# 02_MCU.net
KiCad netlist of a schematic drawn in Altium Designer
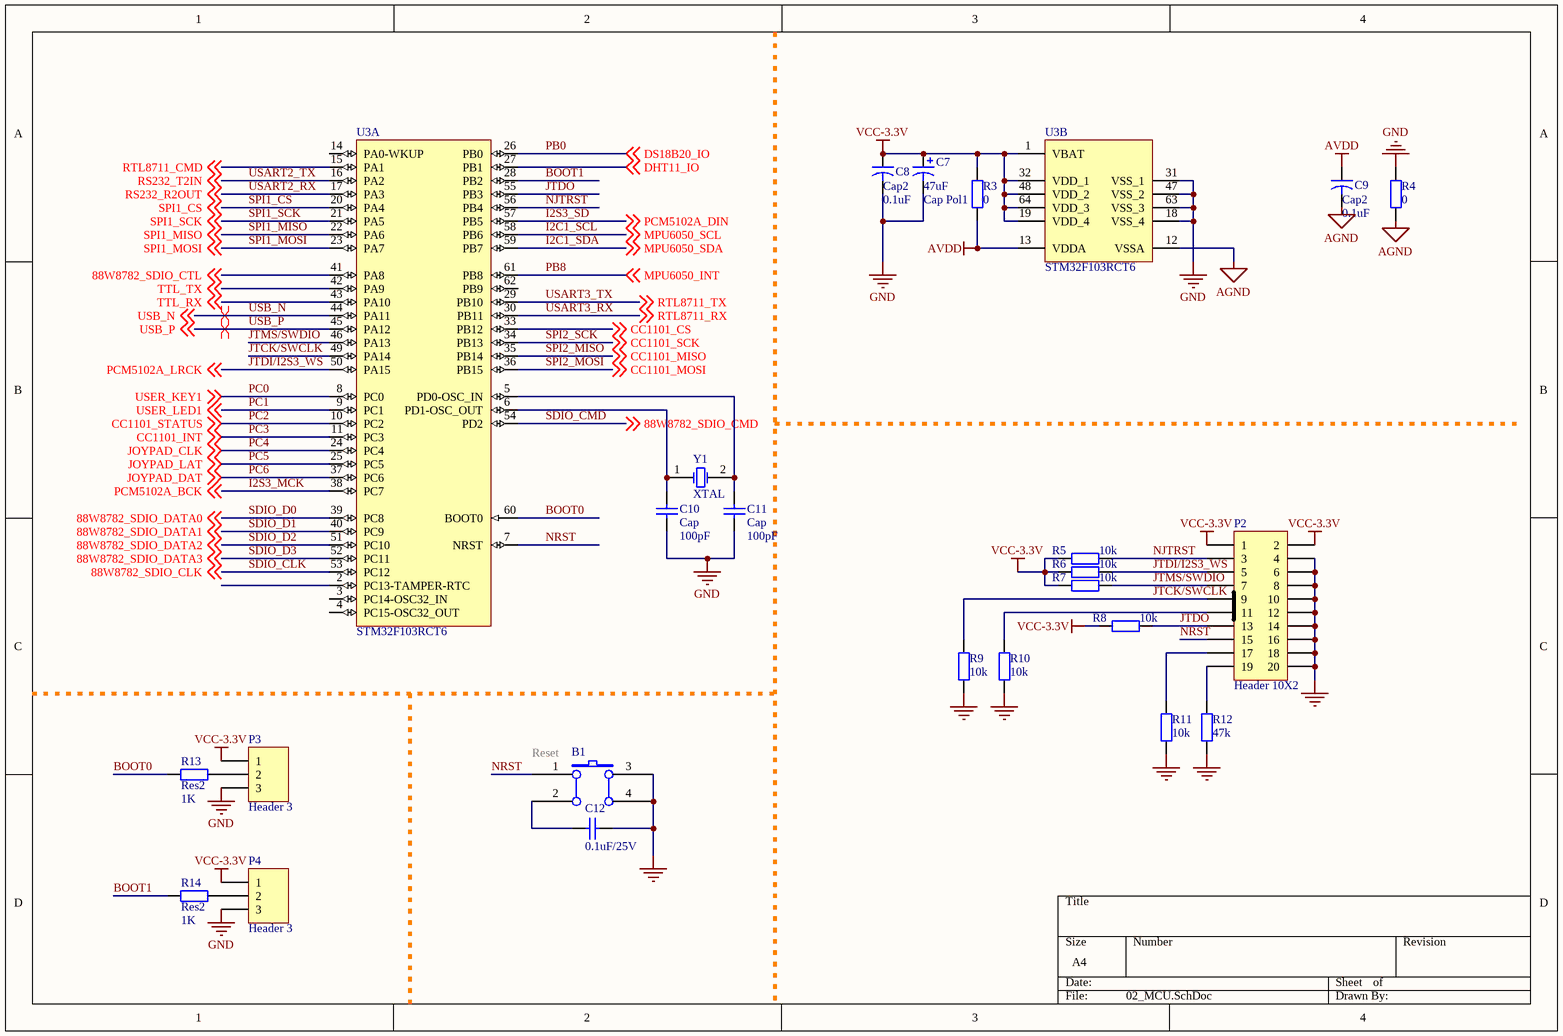
[diagram p0: 02_MCU.SchDoc]

(export (version "E")
  (design (tool "Eeschema 10.0.6"))
  (components
    (comp (ref "B1")
      (value "Reset")
      (footprint "Miscellaneous Modules:SWITCH-0.65/0.45")
      (description "Tactile Switch")
      (libsource (lib "Miscellaneous Modules") (part "SW PUSHBUTTON"))
    )
    (comp (ref "C7")
      (value "Cap Pol1")
      (footprint "RB2.5-6.3")
      (description "Polarized Capacitor (Radial)")
      (fields (field (name "ALTIUM_VALUE") "47uF") (field (name "PUBLISHER") "Altium Limited"))
      (libsource (lib "Miscellaneous Devices") (part "Cap Pol1"))
    )
    (comp (ref "C8")
      (value "Cap2")
      (footprint "CAPR5-4X5")
      (description "Capacitor")
      (fields (field (name "ALTIUM_VALUE") "0.1uF") (field (name "PUBLISHER") "Altium Limited"))
      (libsource (lib "Miscellaneous Devices") (part "Cap2"))
    )
    (comp (ref "C9")
      (value "Cap2")
      (footprint "RAD-0.1")
      (description "Capacitor")
      (fields (field (name "ALTIUM_VALUE") "0.1uF") (field (name "PUBLISHER") "Altium Limited"))
      (libsource (lib "Miscellaneous Devices") (part "Cap2"))
    )
    (comp (ref "C10")
      (value "Cap")
      (footprint "RAD-0.1")
      (description "Capacitor")
      (fields (field (name "ALTIUM_VALUE") "100pF") (field (name "PUBLISHER") "Altium Limited"))
      (libsource (lib "Miscellaneous Devices") (part "Cap"))
    )
    (comp (ref "C11")
      (value "Cap")
      (footprint "RAD-0.1")
      (description "Capacitor")
      (fields (field (name "ALTIUM_VALUE") "100pF") (field (name "PUBLISHER") "Altium Limited"))
      (libsource (lib "Miscellaneous Devices") (part "Cap"))
    )
    (comp (ref "C12")
      (value "0.1uF/25V")
      (footprint "RAD-0.1")
      (description "Capacitor")
      (fields (field (name "PUBLISHER") "Altium Limited"))
      (libsource (lib "Miscellaneous Devices") (part "CAP"))
    )
    (comp (ref "P2")
      (value "Header 10X2")
      (footprint "MHDR2X10_2.54")
      (description "Header, 10-Pin, Dual row")
      (fields (field (name "PUBLISHER") "Altium Limited"))
      (libsource (lib "Miscellaneous Connectors") (part "Header 10X2"))
    )
    (comp (ref "P3")
      (value "Header 3")
      (footprint "HDR1X3")
      (description "Header, 3-Pin")
      (fields (field (name "PUBLISHER") "Altium Limited"))
      (libsource (lib "Miscellaneous Connectors") (part "Header 3"))
    )
    (comp (ref "P4")
      (value "Header 3")
      (footprint "HDR1X3")
      (description "Header, 3-Pin")
      (fields (field (name "PUBLISHER") "Altium Limited"))
      (libsource (lib "Miscellaneous Connectors") (part "Header 3"))
    )
    (comp (ref "R3")
      (value "0")
      (footprint "AXIAL-0.3")
      (description "贴片电阻")
      (fields (field (name "PUBLISHER") "Altium Limited"))
      (libsource (lib "fszhang") (part "Res1"))
    )
    (comp (ref "R4")
      (value "0")
      (footprint "AXIAL-0.3")
      (description "贴片电阻")
      (fields (field (name "Comment") "10k") (field (name "PUBLISHER") "Altium Limited"))
      (libsource (lib "fszhang") (part "Res1"))
    )
    (comp (ref "R5")
      (value "10k")
      (footprint "AXIAL-0.3")
      (description "贴片电阻")
      (fields (field (name "PUBLISHER") "Altium Limited"))
      (libsource (lib "") (part "Res1_1"))
    )
    (comp (ref "R6")
      (value "10k")
      (footprint "AXIAL-0.3")
      (description "贴片电阻")
      (fields (field (name "PUBLISHER") "Altium Limited"))
      (libsource (lib "") (part "Res1_1"))
    )
    (comp (ref "R7")
      (value "10k")
      (footprint "AXIAL-0.3")
      (description "贴片电阻")
      (fields (field (name "PUBLISHER") "Altium Limited"))
      (libsource (lib "") (part "Res1_1"))
    )
    (comp (ref "R8")
      (value "10k")
      (footprint "AXIAL-0.3")
      (description "贴片电阻")
      (fields (field (name "PUBLISHER") "Altium Limited"))
      (libsource (lib "") (part "Res1_1"))
    )
    (comp (ref "R9")
      (value "10k")
      (footprint "AXIAL-0.3")
      (description "贴片电阻")
      (fields (field (name "PUBLISHER") "Altium Limited"))
      (libsource (lib "fszhang") (part "Res1"))
    )
    (comp (ref "R10")
      (value "10k")
      (footprint "AXIAL-0.3")
      (description "贴片电阻")
      (fields (field (name "PUBLISHER") "Altium Limited"))
      (libsource (lib "fszhang") (part "Res1"))
    )
    (comp (ref "R11")
      (value "10k")
      (footprint "AXIAL-0.3")
      (description "贴片电阻")
      (fields (field (name "PUBLISHER") "Altium Limited"))
      (libsource (lib "fszhang") (part "Res1"))
    )
    (comp (ref "R12")
      (value "47k")
      (footprint "AXIAL-0.3")
      (description "贴片电阻")
      (fields (field (name "Comment") "10k") (field (name "PUBLISHER") "Altium Limited"))
      (libsource (lib "fszhang") (part "Res1"))
    )
    (comp (ref "R13")
      (value "Res2")
      (footprint "AXIAL-0.3")
      (description "Resistor")
      (fields (field (name "ALTIUM_VALUE") "1K") (field (name "PUBLISHER") "Altium Limited"))
      (libsource (lib "Miscellaneous Devices") (part "Res2"))
    )
    (comp (ref "R14")
      (value "Res2")
      (footprint "AXIAL-0.3")
      (description "Resistor")
      (fields (field (name "ALTIUM_VALUE") "1K") (field (name "PUBLISHER") "Altium Limited"))
      (libsource (lib "Miscellaneous Devices") (part "Res2"))
    )
    (comp (ref "U3")
      (value "STM32F103RCT6")
      (footprint "STM-LQFP64_M")
      (libsource (lib "STMicroelectronics STM32 F1") (part "STM32F103RCT6"))
    )
    (comp (ref "Y1")
      (value "XTAL")
      (footprint "XTAL1")
      (description "Crystal Oscillator")
      (fields (field (name "PUBLISHER") "Altium Limited"))
      (libsource (lib "Miscellaneous Devices") (part "XTAL"))
    )
  )
  (nets
    (net (code "1") (name "/BOOT0") (class "Default")
      (node (ref "R13") (pin "1") (pinfunction "1_1") (pintype "passive"))
      (node (ref "U3") (pin "60") (pinfunction "BOOT0_60") (pintype "input"))
    )
    (net (code "2") (name "/BOOT1") (class "Default")
      (node (ref "R14") (pin "1") (pinfunction "1_1") (pintype "passive"))
      (node (ref "U3") (pin "28") (pinfunction "PB2_28") (pintype "bidirectional"))
    )
    (net (code "3") (name "/JTCK{slash}SWCLK") (class "Default")
      (node (ref "P2") (pin "9") (pinfunction "9_9") (pintype "passive"))
      (node (ref "R9") (pin "2") (pinfunction "2_2") (pintype "passive"))
      (node (ref "U3") (pin "49") (pinfunction "PA14_49") (pintype "bidirectional"))
    )
    (net (code "4") (name "/JTDO") (class "Default")
      (node (ref "P2") (pin "13") (pinfunction "13_13") (pintype "passive"))
      (node (ref "R8") (pin "2") (pinfunction "2_2") (pintype "passive"))
      (node (ref "U3") (pin "55") (pinfunction "PB3_55") (pintype "bidirectional"))
    )
    (net (code "5") (name "/JTMS{slash}SWDIO") (class "Default")
      (node (ref "P2") (pin "7") (pinfunction "7_7") (pintype "passive"))
      (node (ref "R7") (pin "2") (pinfunction "2_2") (pintype "passive"))
      (node (ref "U3") (pin "46") (pinfunction "PA13_46") (pintype "bidirectional"))
    )
    (net (code "6") (name "/NJTRST") (class "Default")
      (node (ref "P2") (pin "3") (pinfunction "3_3") (pintype "passive"))
      (node (ref "R5") (pin "2") (pinfunction "2_2") (pintype "passive"))
      (node (ref "U3") (pin "56") (pinfunction "PB4_56") (pintype "bidirectional"))
    )
    (net (code "7") (name "/NRST") (class "Default")
      (node (ref "B1") (pin "1") (pinfunction "A0_1") (pintype "passive"))
      (node (ref "P2") (pin "15") (pinfunction "15_15") (pintype "passive"))
      (node (ref "U3") (pin "7") (pinfunction "NRST_7") (pintype "bidirectional"))
    )
    (net (code "8") (name "88W8782_SDIO_CLK") (class "Default")
      (node (ref "U3") (pin "53") (pinfunction "PC12_53") (pintype "bidirectional"))
    )
    (net (code "9") (name "88W8782_SDIO_CMD") (class "Default")
      (node (ref "U3") (pin "54") (pinfunction "PD2_54") (pintype "bidirectional"))
    )
    (net (code "10") (name "88W8782_SDIO_CTL") (class "Default")
      (node (ref "U3") (pin "41") (pinfunction "PA8_41") (pintype "bidirectional"))
    )
    (net (code "11") (name "88W8782_SDIO_DATA0") (class "Default")
      (node (ref "U3") (pin "39") (pinfunction "PC8_39") (pintype "bidirectional"))
    )
    (net (code "12") (name "88W8782_SDIO_DATA1") (class "Default")
      (node (ref "U3") (pin "40") (pinfunction "PC9_40") (pintype "bidirectional"))
    )
    (net (code "13") (name "88W8782_SDIO_DATA2") (class "Default")
      (node (ref "U3") (pin "51") (pinfunction "PC10_51") (pintype "bidirectional"))
    )
    (net (code "14") (name "88W8782_SDIO_DATA3") (class "Default")
      (node (ref "U3") (pin "52") (pinfunction "PC11_52") (pintype "bidirectional"))
    )
    (net (code "15") (name "AGND") (class "Default")
      (node (ref "C9") (pin "2") (pinfunction "2_2") (pintype "passive"))
      (node (ref "R4") (pin "1") (pinfunction "1_1") (pintype "passive"))
      (node (ref "U3") (pin "12") (pinfunction "VSSA_12") (pintype "power_in"))
    )
    (net (code "16") (name "AVDD") (class "Default")
      (node (ref "C9") (pin "1") (pinfunction "1_1") (pintype "passive"))
      (node (ref "R3") (pin "1") (pinfunction "1_1") (pintype "passive"))
      (node (ref "U3") (pin "13") (pinfunction "VDDA_13") (pintype "power_in"))
    )
    (net (code "17") (name "CC1101_CS") (class "Default")
      (node (ref "U3") (pin "33") (pinfunction "PB12_33") (pintype "bidirectional"))
    )
    (net (code "18") (name "CC1101_INT") (class "Default")
      (node (ref "U3") (pin "11") (pinfunction "PC3_11") (pintype "bidirectional"))
    )
    (net (code "19") (name "CC1101_MISO") (class "Default")
      (node (ref "U3") (pin "35") (pinfunction "PB14_35") (pintype "bidirectional"))
    )
    (net (code "20") (name "CC1101_MOSI") (class "Default")
      (node (ref "U3") (pin "36") (pinfunction "PB15_36") (pintype "bidirectional"))
    )
    (net (code "21") (name "CC1101_SCK") (class "Default")
      (node (ref "U3") (pin "34") (pinfunction "PB13_34") (pintype "bidirectional"))
    )
    (net (code "22") (name "CC1101_STATUS") (class "Default")
      (node (ref "U3") (pin "10") (pinfunction "PC2_10") (pintype "bidirectional"))
    )
    (net (code "23") (name "DHT11_IO") (class "Default")
      (node (ref "U3") (pin "27") (pinfunction "PB1_27") (pintype "bidirectional"))
    )
    (net (code "24") (name "DS18B20_IO") (class "Default")
      (node (ref "U3") (pin "26") (pinfunction "PB0_26") (pintype "bidirectional"))
    )
    (net (code "25") (name "GND") (class "Default")
      (node (ref "B1") (pin "3") (pinfunction "B1_3") (pintype "passive"))
      (node (ref "B1") (pin "4") (pinfunction "A1_4") (pintype "passive"))
      (node (ref "C10") (pin "1") (pinfunction "1_1") (pintype "passive"))
      (node (ref "C11") (pin "1") (pinfunction "1_1") (pintype "passive"))
      (node (ref "C12") (pin "1") (pinfunction "1_1") (pintype "passive"))
      (node (ref "C7") (pin "2") (pinfunction "2_2") (pintype "passive"))
      (node (ref "C8") (pin "2") (pinfunction "2_2") (pintype "passive"))
      (node (ref "P2") (pin "10") (pinfunction "10_10") (pintype "passive"))
      (node (ref "P2") (pin "12") (pinfunction "12_12") (pintype "passive"))
      (node (ref "P2") (pin "14") (pinfunction "14_14") (pintype "passive"))
      (node (ref "P2") (pin "16") (pinfunction "16_16") (pintype "passive"))
      (node (ref "P2") (pin "18") (pinfunction "18_18") (pintype "passive"))
      (node (ref "P2") (pin "20") (pinfunction "20_20") (pintype "passive"))
      (node (ref "P2") (pin "4") (pinfunction "4_4") (pintype "passive"))
      (node (ref "P2") (pin "6") (pinfunction "6_6") (pintype "passive"))
      (node (ref "P2") (pin "8") (pinfunction "8_8") (pintype "passive"))
      (node (ref "P3") (pin "3") (pinfunction "3_3") (pintype "passive"))
      (node (ref "P4") (pin "3") (pinfunction "3_3") (pintype "passive"))
      (node (ref "R10") (pin "1") (pinfunction "1_1") (pintype "passive"))
      (node (ref "R11") (pin "1") (pinfunction "1_1") (pintype "passive"))
      (node (ref "R12") (pin "1") (pinfunction "1_1") (pintype "passive"))
      (node (ref "R4") (pin "2") (pinfunction "2_2") (pintype "passive"))
      (node (ref "R9") (pin "1") (pinfunction "1_1") (pintype "passive"))
      (node (ref "U3") (pin "18") (pinfunction "VSS_4_18") (pintype "power_in"))
      (node (ref "U3") (pin "31") (pinfunction "VSS_1_31") (pintype "power_in"))
      (node (ref "U3") (pin "47") (pinfunction "VSS_2_47") (pintype "power_in"))
      (node (ref "U3") (pin "63") (pinfunction "VSS_3_63") (pintype "power_in"))
    )
    (net (code "26") (name "JOYPAD_CLK") (class "Default")
      (node (ref "U3") (pin "24") (pinfunction "PC4_24") (pintype "bidirectional"))
    )
    (net (code "27") (name "JOYPAD_DAT") (class "Default")
      (node (ref "U3") (pin "37") (pinfunction "PC6_37") (pintype "bidirectional"))
    )
    (net (code "28") (name "JOYPAD_LAT") (class "Default")
      (node (ref "U3") (pin "25") (pinfunction "PC5_25") (pintype "bidirectional"))
    )
    (net (code "29") (name "MPU6050_INT") (class "Default")
      (node (ref "U3") (pin "61") (pinfunction "PB8_61") (pintype "bidirectional"))
    )
    (net (code "30") (name "MPU6050_SCL") (class "Default")
      (node (ref "U3") (pin "58") (pinfunction "PB6_58") (pintype "bidirectional"))
    )
    (net (code "31") (name "MPU6050_SDA") (class "Default")
      (node (ref "U3") (pin "59") (pinfunction "PB7_59") (pintype "bidirectional"))
    )
    (net (code "32") (name "Net-(B1-B0)") (class "Default")
      (node (ref "B1") (pin "2") (pinfunction "B0_2") (pintype "passive"))
      (node (ref "C12") (pin "2") (pinfunction "2_2") (pintype "passive"))
    )
    (net (code "33") (name "Net-(P2-Pad11)") (class "Default")
      (node (ref "P2") (pin "11") (pinfunction "11_11") (pintype "passive"))
      (node (ref "R10") (pin "2") (pinfunction "2_2") (pintype "passive"))
    )
    (net (code "34") (name "Net-(P2-Pad17)") (class "Default")
      (node (ref "P2") (pin "17") (pinfunction "17_17") (pintype "passive"))
      (node (ref "R11") (pin "2") (pinfunction "2_2") (pintype "passive"))
    )
    (net (code "35") (name "Net-(P2-Pad19)") (class "Default")
      (node (ref "P2") (pin "19") (pinfunction "19_19") (pintype "passive"))
      (node (ref "R12") (pin "2") (pinfunction "2_2") (pintype "passive"))
    )
    (net (code "36") (name "Net-(P3-Pad2)") (class "Default")
      (node (ref "P3") (pin "2") (pinfunction "2_2") (pintype "passive"))
      (node (ref "R13") (pin "2") (pinfunction "2_2") (pintype "passive"))
    )
    (net (code "37") (name "Net-(P4-Pad2)") (class "Default")
      (node (ref "P4") (pin "2") (pinfunction "2_2") (pintype "passive"))
      (node (ref "R14") (pin "2") (pinfunction "2_2") (pintype "passive"))
    )
    (net (code "38") (name "Net-(U3A-PD0-OSC_IN)") (class "Default")
      (node (ref "C11") (pin "2") (pinfunction "2_2") (pintype "passive"))
      (node (ref "U3") (pin "5") (pinfunction "PD0-OSC_IN_5") (pintype "bidirectional"))
      (node (ref "Y1") (pin "2") (pinfunction "OSC2_2") (pintype "passive"))
    )
    (net (code "39") (name "Net-(U3A-PD1-OSC_OUT)") (class "Default")
      (node (ref "C10") (pin "2") (pinfunction "2_2") (pintype "passive"))
      (node (ref "U3") (pin "6") (pinfunction "PD1-OSC_OUT_6") (pintype "bidirectional"))
      (node (ref "Y1") (pin "1") (pinfunction "OSC1_1") (pintype "passive"))
    )
    (net (code "40") (name "PCM5102A_BCK") (class "Default")
      (node (ref "U3") (pin "38") (pinfunction "PC7_38") (pintype "bidirectional"))
    )
    (net (code "41") (name "PCM5102A_DIN") (class "Default")
      (node (ref "U3") (pin "57") (pinfunction "PB5_57") (pintype "bidirectional"))
    )
    (net (code "42") (name "PCM5102A_LRCK") (class "Default")
      (node (ref "P2") (pin "5") (pinfunction "5_5") (pintype "passive"))
      (node (ref "R6") (pin "2") (pinfunction "2_2") (pintype "passive"))
      (node (ref "U3") (pin "50") (pinfunction "PA15_50") (pintype "bidirectional"))
    )
    (net (code "43") (name "RS232_R2OUT") (class "Default")
      (node (ref "U3") (pin "17") (pinfunction "PA3_17") (pintype "bidirectional"))
    )
    (net (code "44") (name "RS232_T2IN") (class "Default")
      (node (ref "U3") (pin "16") (pinfunction "PA2_16") (pintype "bidirectional"))
    )
    (net (code "45") (name "RTL8711_CMD") (class "Default")
      (node (ref "U3") (pin "15") (pinfunction "PA1_15") (pintype "bidirectional"))
    )
    (net (code "46") (name "RTL8711_RX") (class "Default")
      (node (ref "U3") (pin "30") (pinfunction "PB11_30") (pintype "bidirectional"))
    )
    (net (code "47") (name "RTL8711_TX") (class "Default")
      (node (ref "U3") (pin "29") (pinfunction "PB10_29") (pintype "bidirectional"))
    )
    (net (code "48") (name "SPI1_CS") (class "Default")
      (node (ref "U3") (pin "20") (pinfunction "PA4_20") (pintype "bidirectional"))
    )
    (net (code "49") (name "SPI1_MISO") (class "Default")
      (node (ref "U3") (pin "22") (pinfunction "PA6_22") (pintype "bidirectional"))
    )
    (net (code "50") (name "SPI1_MOSI") (class "Default")
      (node (ref "U3") (pin "23") (pinfunction "PA7_23") (pintype "bidirectional"))
    )
    (net (code "51") (name "SPI1_SCK") (class "Default")
      (node (ref "U3") (pin "21") (pinfunction "PA5_21") (pintype "bidirectional"))
    )
    (net (code "52") (name "TTL_RX") (class "Default")
      (node (ref "U3") (pin "43") (pinfunction "PA10_43") (pintype "bidirectional"))
    )
    (net (code "53") (name "TTL_TX") (class "Default")
      (node (ref "U3") (pin "42") (pinfunction "PA9_42") (pintype "bidirectional"))
    )
    (net (code "54") (name "USB_N") (class "Default")
      (node (ref "U3") (pin "44") (pinfunction "PA11_44") (pintype "bidirectional"))
    )
    (net (code "55") (name "USB_P") (class "Default")
      (node (ref "U3") (pin "45") (pinfunction "PA12_45") (pintype "bidirectional"))
    )
    (net (code "56") (name "USER_KEY1") (class "Default")
      (node (ref "U3") (pin "8") (pinfunction "PC0_8") (pintype "bidirectional"))
    )
    (net (code "57") (name "USER_LED1") (class "Default")
      (node (ref "U3") (pin "9") (pinfunction "PC1_9") (pintype "bidirectional"))
    )
    (net (code "58") (name "VCC-3.3V") (class "Default")
      (node (ref "C7") (pin "1") (pinfunction "1_1") (pintype "passive"))
      (node (ref "C8") (pin "1") (pinfunction "1_1") (pintype "passive"))
      (node (ref "P2") (pin "1") (pinfunction "1_1") (pintype "passive"))
      (node (ref "P2") (pin "2") (pinfunction "2_2") (pintype "passive"))
      (node (ref "P3") (pin "1") (pinfunction "1_1") (pintype "passive"))
      (node (ref "P4") (pin "1") (pinfunction "1_1") (pintype "passive"))
      (node (ref "R3") (pin "2") (pinfunction "2_2") (pintype "passive"))
      (node (ref "R5") (pin "1") (pinfunction "1_1") (pintype "passive"))
      (node (ref "R6") (pin "1") (pinfunction "1_1") (pintype "passive"))
      (node (ref "R7") (pin "1") (pinfunction "1_1") (pintype "passive"))
      (node (ref "R8") (pin "1") (pinfunction "1_1") (pintype "passive"))
      (node (ref "U3") (pin "1") (pinfunction "VBAT_1") (pintype "power_in"))
      (node (ref "U3") (pin "19") (pinfunction "VDD_4_19") (pintype "power_in"))
      (node (ref "U3") (pin "32") (pinfunction "VDD_1_32") (pintype "power_in"))
      (node (ref "U3") (pin "48") (pinfunction "VDD_2_48") (pintype "power_in"))
      (node (ref "U3") (pin "64") (pinfunction "VDD_3_64") (pintype "power_in"))
    )
    (net (code "59") (name "unconnected-(U3A-PA0-WKUP-Pad14)") (class "Default")
      (node (ref "U3") (pin "14") (pinfunction "PA0-WKUP_14") (pintype "bidirectional"))
    )
    (net (code "60") (name "unconnected-(U3A-PB9-Pad62)") (class "Default")
      (node (ref "U3") (pin "62") (pinfunction "PB9_62") (pintype "bidirectional"))
    )
    (net (code "61") (name "unconnected-(U3A-PC13-TAMPER-RTC-Pad2)") (class "Default")
      (node (ref "U3") (pin "2") (pinfunction "PC13-TAMPER-RTC_2") (pintype "bidirectional"))
    )
    (net (code "62") (name "unconnected-(U3A-PC14-OSC32_IN-Pad3)") (class "Default")
      (node (ref "U3") (pin "3") (pinfunction "PC14-OSC32_IN_3") (pintype "bidirectional"))
    )
    (net (code "63") (name "unconnected-(U3A-PC15-OSC32_OUT-Pad4)") (class "Default")
      (node (ref "U3") (pin "4") (pinfunction "PC15-OSC32_OUT_4") (pintype "bidirectional"))
    )
  )
)
